# Omni-BASIC-BOTTOM.net
KiCad netlist of a schematic drawn in EAGLE
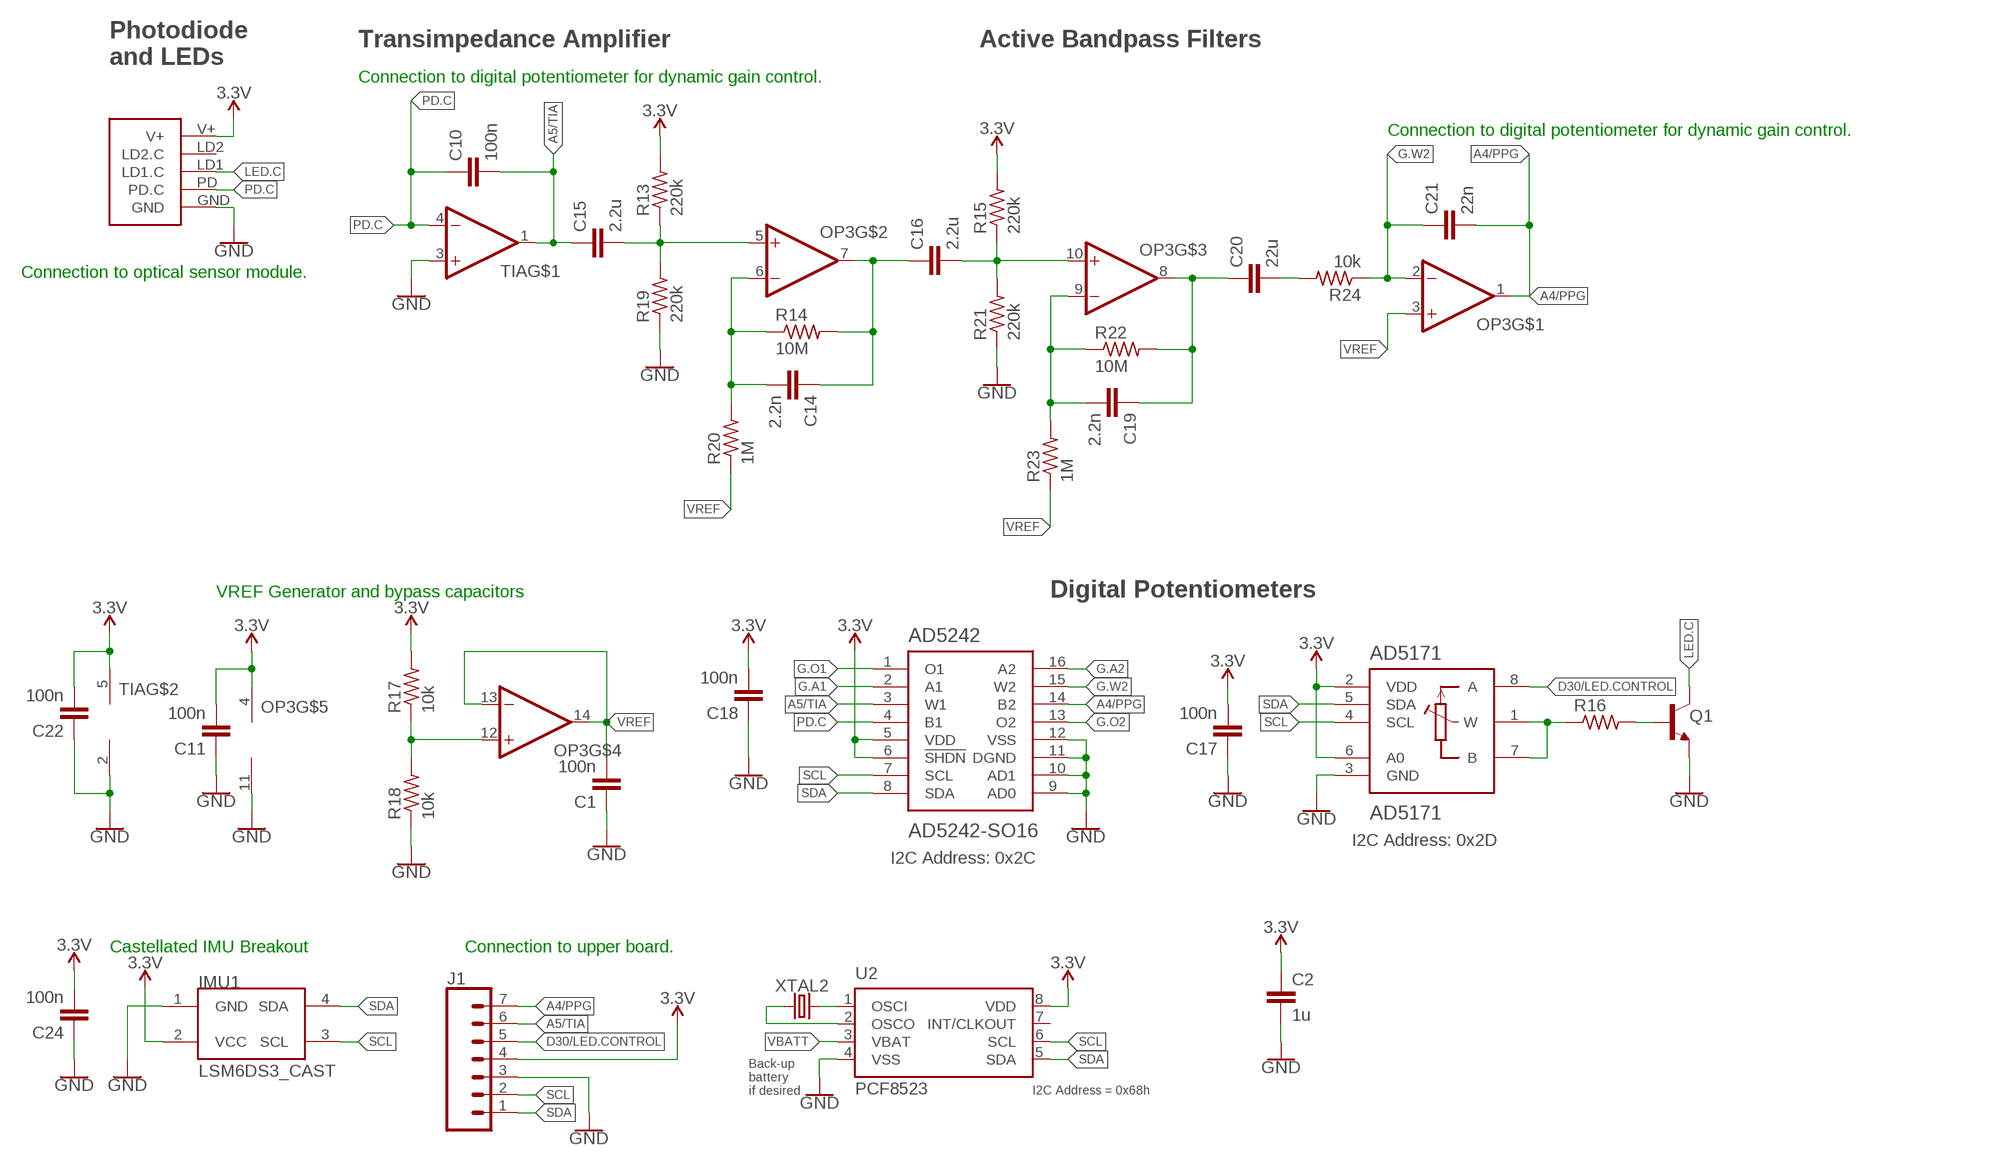
[diagram p0: schematic, sheet 1]

(export (version "E")
  (design (tool "Eeschema 10.0.6"))
  (components
    (comp (ref "AD5171")
      (value "AD5171")
      (footprint "eagle-import:SOT-23-8")
      (libsource (lib "eagle-import") (part "AD5171"))
    )
    (comp (ref "AD5242")
      (value "AD5242-SO16")
      (footprint "eagle-import:SO16")
      (libsource (lib "eagle-import") (part "AD5242-SO16"))
    )
    (comp (ref "C1")
      (value "100n")
      (footprint "eagle-import:C0603")
      (libsource (lib "eagle-import") (part "CAPACITOR0603"))
    )
    (comp (ref "C2")
      (value "1u")
      (footprint "eagle-import:C0603")
      (libsource (lib "eagle-import") (part "CAPACITOR0603"))
    )
    (comp (ref "C10")
      (value "100n")
      (footprint "eagle-import:C0603")
      (libsource (lib "eagle-import") (part "CAPACITOR0603"))
    )
    (comp (ref "C11")
      (value "100n")
      (footprint "eagle-import:C0603")
      (libsource (lib "eagle-import") (part "CAPACITOR0603"))
    )
    (comp (ref "C14")
      (value "2.2n")
      (footprint "eagle-import:C0603")
      (libsource (lib "eagle-import") (part "CAPACITOR0603"))
    )
    (comp (ref "C15")
      (value "2.2u")
      (footprint "eagle-import:C0603")
      (libsource (lib "eagle-import") (part "CAPACITOR0603"))
    )
    (comp (ref "C16")
      (value "2.2u")
      (footprint "eagle-import:C0603")
      (libsource (lib "eagle-import") (part "CAPACITOR0603"))
    )
    (comp (ref "C17")
      (value "100n")
      (footprint "eagle-import:C0603")
      (libsource (lib "eagle-import") (part "CAPACITOR0603"))
    )
    (comp (ref "C18")
      (value "100n")
      (footprint "eagle-import:C0603")
      (libsource (lib "eagle-import") (part "CAPACITOR0603"))
    )
    (comp (ref "C19")
      (value "2.2n")
      (footprint "eagle-import:C0603")
      (libsource (lib "eagle-import") (part "CAPACITOR0603"))
    )
    (comp (ref "C20")
      (value "22u")
      (footprint "eagle-import:C0603")
      (libsource (lib "eagle-import") (part "CAPACITOR0603"))
    )
    (comp (ref "C21")
      (value "22n")
      (footprint "eagle-import:C0603")
      (libsource (lib "eagle-import") (part "CAPACITOR0603"))
    )
    (comp (ref "C22")
      (value "100n")
      (footprint "eagle-import:C0603")
      (libsource (lib "eagle-import") (part "CAPACITOR0603"))
    )
    (comp (ref "C24")
      (value "100n")
      (footprint "eagle-import:C0603")
      (libsource (lib "eagle-import") (part "CAPACITOR0603"))
    )
    (comp (ref "IMU1")
      (value "LSM6DS3_CAST")
      (footprint "eagle-import:LSM6DS3_CAST")
      (libsource (lib "eagle-import") (part "LSM6DS3_CAST"))
    )
    (comp (ref "J1")
      (value "CONN_07-1.27MM")
      (footprint "eagle-import:1X07_1.27MM")
      (libsource (lib "eagle-import") (part "CONN_07-1.27MM"))
    )
    (comp (ref "OP3")
      (value "OP-QUAD-SO14")
      (footprint "eagle-import:SO14")
      (libsource (lib "eagle-import") (part "OP-QUAD-SO14"))
    )
    (comp (ref "Q1")
      (value "NPN-GENERIC")
      (footprint "eagle-import:SOT23-3")
      (libsource (lib "eagle-import") (part "NPN-GENERIC"))
    )
    (comp (ref "R13")
      (value "220k")
      (footprint "eagle-import:R0603")
      (libsource (lib "eagle-import") (part "RESISTOR0603"))
    )
    (comp (ref "R14")
      (value "10M")
      (footprint "eagle-import:R0603")
      (libsource (lib "eagle-import") (part "RESISTOR0603"))
    )
    (comp (ref "R15")
      (value "220k")
      (footprint "eagle-import:R0603")
      (libsource (lib "eagle-import") (part "RESISTOR0603"))
    )
    (comp (ref "R16")
      (value "RESISTOR0603")
      (footprint "eagle-import:R0603")
      (libsource (lib "eagle-import") (part "RESISTOR0603"))
    )
    (comp (ref "R17")
      (value "10k")
      (footprint "eagle-import:R0402")
      (libsource (lib "eagle-import") (part "RESISTOR0402"))
    )
    (comp (ref "R18")
      (value "10k")
      (footprint "eagle-import:R0402")
      (libsource (lib "eagle-import") (part "RESISTOR0402"))
    )
    (comp (ref "R19")
      (value "220k")
      (footprint "eagle-import:R0603")
      (libsource (lib "eagle-import") (part "RESISTOR0603"))
    )
    (comp (ref "R20")
      (value "1M")
      (footprint "eagle-import:R0603")
      (libsource (lib "eagle-import") (part "RESISTOR0603"))
    )
    (comp (ref "R21")
      (value "220k")
      (footprint "eagle-import:R0603")
      (libsource (lib "eagle-import") (part "RESISTOR0603"))
    )
    (comp (ref "R22")
      (value "10M")
      (footprint "eagle-import:R0603")
      (libsource (lib "eagle-import") (part "RESISTOR0603"))
    )
    (comp (ref "R23")
      (value "1M")
      (footprint "eagle-import:R0603")
      (libsource (lib "eagle-import") (part "RESISTOR0603"))
    )
    (comp (ref "R24")
      (value "10k")
      (footprint "eagle-import:R0603")
      (libsource (lib "eagle-import") (part "RESISTOR0603"))
    )
    (comp (ref "TIA")
      (value "OP-SINGLEOT")
      (footprint "eagle-import:SOT23-5")
      (libsource (lib "eagle-import") (part "OP-SINGLEOT"))
    )
    (comp (ref "U$3")
      (value "PPG.MODULE.2")
      (footprint "eagle-import:PPG.MODULE.2")
      (libsource (lib "eagle-import") (part "PPG.MODULE.2"))
    )
    (comp (ref "U2")
      (value "PCF8523")
      (footprint "eagle-import:SO8")
      (libsource (lib "eagle-import") (part "PCF8523"))
    )
    (comp (ref "XTAL2")
      (value "32.7680kHz")
      (footprint "eagle-import:2-SMD.NOLEAD.2.0MMTO1.2MM")
      (fields (field (name "FREQ") "32.7680KHZ"))
      (libsource (lib "eagle-import") (part "CRYSTALECS-.327-12.5-12-C-TR"))
    )
  )
  (nets
    (net (code "1") (name "3.3V") (class "Default")
      (node (ref "AD5171") (pin "2") (pinfunction "VDD_2") (pintype "bidirectional"))
      (node (ref "AD5171") (pin "6") (pinfunction "A0_6") (pintype "bidirectional"))
      (node (ref "AD5242") (pin "5") (pinfunction "VDD_5") (pintype "bidirectional"))
      (node (ref "AD5242") (pin "6") (pinfunction "~{SHDN}_6") (pintype "bidirectional"))
      (node (ref "C11") (pin "2") (pinfunction "2_2") (pintype "passive"))
      (node (ref "C17") (pin "2") (pinfunction "2_2") (pintype "passive"))
      (node (ref "C18") (pin "2") (pinfunction "2_2") (pintype "passive"))
      (node (ref "C2") (pin "1") (pinfunction "1_1") (pintype "passive"))
      (node (ref "C22") (pin "2") (pinfunction "2_2") (pintype "passive"))
      (node (ref "C24") (pin "2") (pinfunction "2_2") (pintype "passive"))
      (node (ref "IMU1") (pin "2") (pinfunction "VCC_2") (pintype "bidirectional"))
      (node (ref "J1") (pin "4") (pinfunction "4_4") (pintype "passive"))
      (node (ref "OP3") (pin "4") (pinfunction "V+_4") (pintype "power_in"))
      (node (ref "R13") (pin "2") (pinfunction "2_2") (pintype "passive"))
      (node (ref "R15") (pin "2") (pinfunction "2_2") (pintype "passive"))
      (node (ref "R17") (pin "2") (pinfunction "2_2") (pintype "passive"))
      (node (ref "TIA") (pin "5") (pinfunction "V+_5") (pintype "power_in"))
      (node (ref "U$3") (pin "V+") (pinfunction "V+_V+") (pintype "bidirectional"))
      (node (ref "U2") (pin "8") (pinfunction "VDD_8") (pintype "power_in"))
    )
    (net (code "2") (name "A4{slash}PPG") (class "Default")
      (node (ref "AD5242") (pin "14") (pinfunction "B2_14") (pintype "bidirectional"))
      (node (ref "C21") (pin "2") (pinfunction "2_2") (pintype "passive"))
      (node (ref "J1") (pin "7") (pinfunction "7_7") (pintype "passive"))
      (node (ref "OP3") (pin "1") (pinfunction "OUT_1") (pintype "output"))
    )
    (net (code "3") (name "A5{slash}TIA") (class "Default")
      (node (ref "AD5242") (pin "3") (pinfunction "W1_3") (pintype "bidirectional"))
      (node (ref "C10") (pin "2") (pinfunction "2_2") (pintype "passive"))
      (node (ref "C15") (pin "1") (pinfunction "1_1") (pintype "passive"))
      (node (ref "J1") (pin "6") (pinfunction "6_6") (pintype "passive"))
      (node (ref "TIA") (pin "1") (pinfunction "OUT_1") (pintype "output"))
    )
    (net (code "4") (name "D30{slash}LED.CONTROL") (class "Default")
      (node (ref "AD5171") (pin "8") (pinfunction "A_8") (pintype "bidirectional"))
      (node (ref "J1") (pin "5") (pinfunction "5_5") (pintype "passive"))
    )
    (net (code "5") (name "G.A1") (class "Default")
      (node (ref "AD5242") (pin "2") (pinfunction "A1_2") (pintype "bidirectional"))
    )
    (net (code "6") (name "G.A2") (class "Default")
      (node (ref "AD5242") (pin "16") (pinfunction "A2_16") (pintype "bidirectional"))
    )
    (net (code "7") (name "G.O1") (class "Default")
      (node (ref "AD5242") (pin "1") (pinfunction "O1_1") (pintype "bidirectional"))
    )
    (net (code "8") (name "G.O2") (class "Default")
      (node (ref "AD5242") (pin "13") (pinfunction "O2_13") (pintype "bidirectional"))
    )
    (net (code "9") (name "G.W2") (class "Default")
      (node (ref "AD5242") (pin "15") (pinfunction "W2_15") (pintype "bidirectional"))
      (node (ref "C21") (pin "1") (pinfunction "1_1") (pintype "passive"))
      (node (ref "OP3") (pin "2") (pinfunction "-IN_2") (pintype "input"))
      (node (ref "R24") (pin "1") (pinfunction "1_1") (pintype "passive"))
    )
    (net (code "10") (name "GND") (class "Default")
      (node (ref "AD5171") (pin "3") (pinfunction "GND_3") (pintype "bidirectional"))
      (node (ref "AD5242") (pin "10") (pinfunction "AD1_10") (pintype "bidirectional"))
      (node (ref "AD5242") (pin "11") (pinfunction "DGND_11") (pintype "bidirectional"))
      (node (ref "AD5242") (pin "12") (pinfunction "VSS_12") (pintype "bidirectional"))
      (node (ref "AD5242") (pin "9") (pinfunction "AD0_9") (pintype "bidirectional"))
      (node (ref "C1") (pin "1") (pinfunction "1_1") (pintype "passive"))
      (node (ref "C11") (pin "1") (pinfunction "1_1") (pintype "passive"))
      (node (ref "C17") (pin "1") (pinfunction "1_1") (pintype "passive"))
      (node (ref "C18") (pin "1") (pinfunction "1_1") (pintype "passive"))
      (node (ref "C2") (pin "2") (pinfunction "2_2") (pintype "passive"))
      (node (ref "C22") (pin "1") (pinfunction "1_1") (pintype "passive"))
      (node (ref "C24") (pin "1") (pinfunction "1_1") (pintype "passive"))
      (node (ref "IMU1") (pin "1") (pinfunction "GND_1") (pintype "bidirectional"))
      (node (ref "J1") (pin "3") (pinfunction "3_3") (pintype "passive"))
      (node (ref "OP3") (pin "11") (pinfunction "V-_11") (pintype "power_in"))
      (node (ref "Q1") (pin "2") (pinfunction "E_2") (pintype "passive"))
      (node (ref "R18") (pin "1") (pinfunction "1_1") (pintype "passive"))
      (node (ref "R19") (pin "1") (pinfunction "1_1") (pintype "passive"))
      (node (ref "R21") (pin "1") (pinfunction "1_1") (pintype "passive"))
      (node (ref "TIA") (pin "2") (pinfunction "V-_2") (pintype "power_in"))
      (node (ref "TIA") (pin "3") (pinfunction "+IN_3") (pintype "input"))
      (node (ref "U$3") (pin "GND") (pinfunction "GND_GND") (pintype "bidirectional"))
      (node (ref "U2") (pin "4") (pinfunction "VSS_4") (pintype "power_in"))
    )
    (net (code "11") (name "LED.C") (class "Default")
      (node (ref "Q1") (pin "3") (pinfunction "C_3") (pintype "passive"))
      (node (ref "U$3") (pin "LD1") (pinfunction "LD1.C_LD1") (pintype "bidirectional"))
    )
    (net (code "12") (name "Net-(AD5171-B)") (class "Default")
      (node (ref "AD5171") (pin "1") (pinfunction "W_1") (pintype "bidirectional"))
      (node (ref "AD5171") (pin "7") (pinfunction "B_7") (pintype "bidirectional"))
      (node (ref "R16") (pin "1") (pinfunction "1_1") (pintype "passive"))
    )
    (net (code "13") (name "Net-(C20-Pad2)") (class "Default")
      (node (ref "C20") (pin "2") (pinfunction "2_2") (pintype "passive"))
      (node (ref "R24") (pin "2") (pinfunction "2_2") (pintype "passive"))
    )
    (net (code "14") (name "Net-(OP3B-+IN)") (class "Default")
      (node (ref "C15") (pin "2") (pinfunction "2_2") (pintype "passive"))
      (node (ref "OP3") (pin "5") (pinfunction "+IN_5") (pintype "input"))
      (node (ref "R13") (pin "1") (pinfunction "1_1") (pintype "passive"))
      (node (ref "R19") (pin "2") (pinfunction "2_2") (pintype "passive"))
    )
    (net (code "15") (name "Net-(OP3B--IN)") (class "Default")
      (node (ref "C14") (pin "2") (pinfunction "2_2") (pintype "passive"))
      (node (ref "OP3") (pin "6") (pinfunction "-IN_6") (pintype "input"))
      (node (ref "R14") (pin "1") (pinfunction "1_1") (pintype "passive"))
      (node (ref "R20") (pin "2") (pinfunction "2_2") (pintype "passive"))
    )
    (net (code "16") (name "Net-(OP3B-OUT)") (class "Default")
      (node (ref "C14") (pin "1") (pinfunction "1_1") (pintype "passive"))
      (node (ref "C16") (pin "1") (pinfunction "1_1") (pintype "passive"))
      (node (ref "OP3") (pin "7") (pinfunction "OUT_7") (pintype "output"))
      (node (ref "R14") (pin "2") (pinfunction "2_2") (pintype "passive"))
    )
    (net (code "17") (name "Net-(OP3C-+IN)") (class "Default")
      (node (ref "C16") (pin "2") (pinfunction "2_2") (pintype "passive"))
      (node (ref "OP3") (pin "10") (pinfunction "+IN_10") (pintype "input"))
      (node (ref "R15") (pin "1") (pinfunction "1_1") (pintype "passive"))
      (node (ref "R21") (pin "2") (pinfunction "2_2") (pintype "passive"))
    )
    (net (code "18") (name "Net-(OP3C--IN)") (class "Default")
      (node (ref "C19") (pin "2") (pinfunction "2_2") (pintype "passive"))
      (node (ref "OP3") (pin "9") (pinfunction "-IN_9") (pintype "input"))
      (node (ref "R22") (pin "1") (pinfunction "1_1") (pintype "passive"))
      (node (ref "R23") (pin "2") (pinfunction "2_2") (pintype "passive"))
    )
    (net (code "19") (name "Net-(OP3C-OUT)") (class "Default")
      (node (ref "C19") (pin "1") (pinfunction "1_1") (pintype "passive"))
      (node (ref "C20") (pin "1") (pinfunction "1_1") (pintype "passive"))
      (node (ref "OP3") (pin "8") (pinfunction "OUT_8") (pintype "output"))
      (node (ref "R22") (pin "2") (pinfunction "2_2") (pintype "passive"))
    )
    (net (code "20") (name "Net-(OP3D-+IN)") (class "Default")
      (node (ref "OP3") (pin "12") (pinfunction "+IN_12") (pintype "input"))
      (node (ref "R17") (pin "1") (pinfunction "1_1") (pintype "passive"))
      (node (ref "R18") (pin "2") (pinfunction "2_2") (pintype "passive"))
    )
    (net (code "21") (name "Net-(Q1-B)") (class "Default")
      (node (ref "Q1") (pin "1") (pinfunction "B_1") (pintype "passive"))
      (node (ref "R16") (pin "2") (pinfunction "2_2") (pintype "passive"))
    )
    (net (code "22") (name "Net-(U2-OSCI)") (class "Default")
      (node (ref "U2") (pin "1") (pinfunction "OSCI_1") (pintype "bidirectional"))
      (node (ref "XTAL2") (pin "P$2") (pinfunction "2_P$2") (pintype "passive"))
    )
    (net (code "23") (name "Net-(U2-OSCO)") (class "Default")
      (node (ref "U2") (pin "2") (pinfunction "OSCO_2") (pintype "bidirectional"))
      (node (ref "XTAL2") (pin "P$1") (pinfunction "1_P$1") (pintype "passive"))
    )
    (net (code "24") (name "PD.C") (class "Default")
      (node (ref "AD5242") (pin "4") (pinfunction "B1_4") (pintype "bidirectional"))
      (node (ref "C10") (pin "1") (pinfunction "1_1") (pintype "passive"))
      (node (ref "TIA") (pin "4") (pinfunction "-IN_4") (pintype "input"))
      (node (ref "U$3") (pin "PD") (pinfunction "PD.C_PD") (pintype "bidirectional"))
    )
    (net (code "25") (name "SCL") (class "Default")
      (node (ref "AD5171") (pin "4") (pinfunction "SCL_4") (pintype "bidirectional"))
      (node (ref "AD5242") (pin "7") (pinfunction "SCL_7") (pintype "bidirectional"))
      (node (ref "IMU1") (pin "3") (pinfunction "SCL_3") (pintype "bidirectional"))
      (node (ref "J1") (pin "2") (pinfunction "2_2") (pintype "passive"))
      (node (ref "U2") (pin "6") (pinfunction "SCL_6") (pintype "bidirectional"))
    )
    (net (code "26") (name "SDA") (class "Default")
      (node (ref "AD5171") (pin "5") (pinfunction "SDA_5") (pintype "bidirectional"))
      (node (ref "AD5242") (pin "8") (pinfunction "SDA_8") (pintype "bidirectional"))
      (node (ref "IMU1") (pin "4") (pinfunction "SDA_4") (pintype "bidirectional"))
      (node (ref "J1") (pin "1") (pinfunction "1_1") (pintype "passive"))
      (node (ref "U2") (pin "5") (pinfunction "SDA_5") (pintype "bidirectional"))
    )
    (net (code "27") (name "VBATT") (class "Default")
      (node (ref "U2") (pin "3") (pinfunction "VBAT_3") (pintype "power_in"))
    )
    (net (code "28") (name "VREF") (class "Default")
      (node (ref "C1") (pin "2") (pinfunction "2_2") (pintype "passive"))
      (node (ref "OP3") (pin "13") (pinfunction "-IN_13") (pintype "input"))
      (node (ref "OP3") (pin "14") (pinfunction "OUT_14") (pintype "output"))
      (node (ref "OP3") (pin "3") (pinfunction "+IN_3") (pintype "input"))
      (node (ref "R20") (pin "1") (pinfunction "1_1") (pintype "passive"))
      (node (ref "R23") (pin "1") (pinfunction "1_1") (pintype "passive"))
    )
    (net (code "29") (name "unconnected-(U$3-LD2.C-PadLD2)") (class "Default")
      (node (ref "U$3") (pin "LD2") (pinfunction "LD2.C_LD2") (pintype "bidirectional"))
    )
    (net (code "30") (name "unconnected-(U2-INT{slash}CLKOUT-Pad7)") (class "Default")
      (node (ref "U2") (pin "7") (pinfunction "INT/CLKOUT_7") (pintype "bidirectional"))
    )
  )
)
